# Tetris.net
KiCad netlist of a schematic drawn in EAGLE
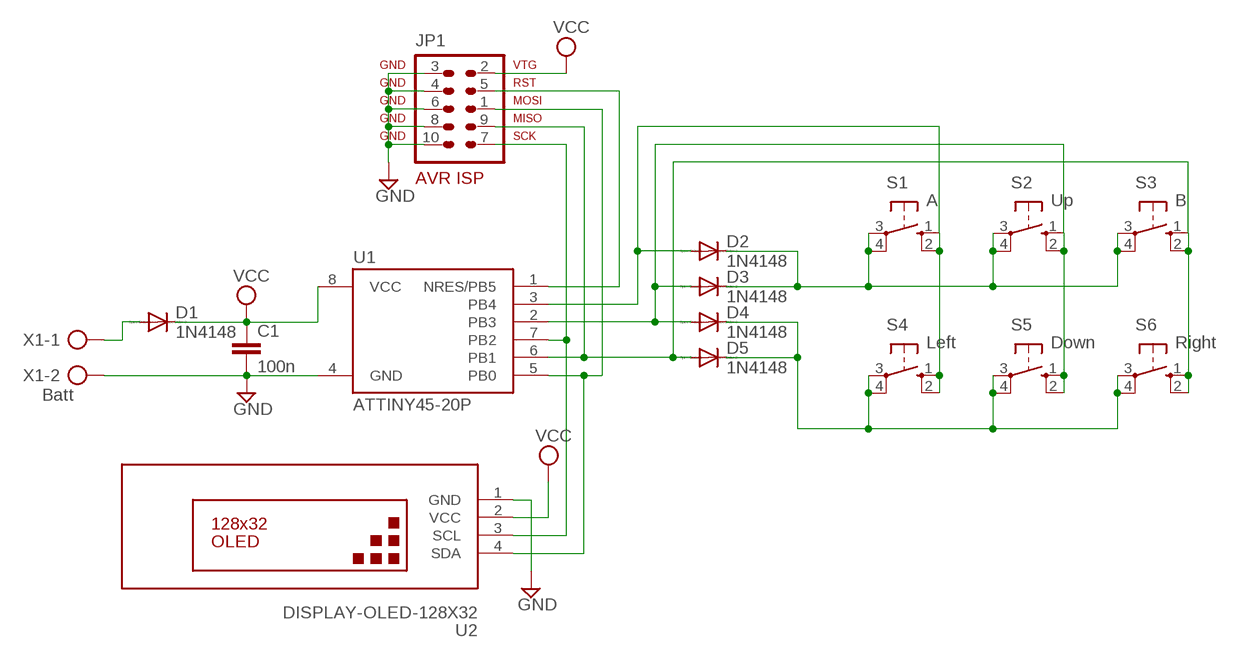
[diagram p0: schematic, sheet 1]

(export (version "E")
  (design (tool "Eeschema 10.0.6"))
  (components
    (comp (ref "C1")
      (value "100n")
      (footprint "eagle-import:C025-024X044")
      (libsource (lib "eagle-import") (part "C-EU025-024X044"))
    )
    (comp (ref "D1")
      (value "1N4148")
      (footprint "eagle-import:DO35-7")
      (libsource (lib "eagle-import") (part "1N4148DO35-7"))
    )
    (comp (ref "D2")
      (value "1N4148")
      (footprint "eagle-import:DO35-7")
      (libsource (lib "eagle-import") (part "1N4148DO35-7"))
    )
    (comp (ref "D3")
      (value "1N4148")
      (footprint "eagle-import:DO35-7")
      (libsource (lib "eagle-import") (part "1N4148DO35-7"))
    )
    (comp (ref "D4")
      (value "1N4148")
      (footprint "eagle-import:DO35-7")
      (libsource (lib "eagle-import") (part "1N4148DO35-7"))
    )
    (comp (ref "D5")
      (value "1N4148")
      (footprint "eagle-import:DO35-7")
      (libsource (lib "eagle-import") (part "1N4148DO35-7"))
    )
    (comp (ref "JP1")
      (value "AVR-ISP-10")
      (footprint "eagle-import:AVR-ISP-10")
      (libsource (lib "eagle-import") (part "AVR-ISP-10"))
    )
    (comp (ref "S1")
      (value "A")
      (footprint "eagle-import:B3F-10XX")
      (fields (field (name "MPN") "B3F-1000"))
      (libsource (lib "eagle-import") (part "10-XX"))
    )
    (comp (ref "S2")
      (value "Up")
      (footprint "eagle-import:B3F-10XX")
      (fields (field (name "MPN") "B3F-1000"))
      (libsource (lib "eagle-import") (part "10-XX"))
    )
    (comp (ref "S3")
      (value "B")
      (footprint "eagle-import:B3F-10XX")
      (fields (field (name "MPN") "B3F-1000"))
      (libsource (lib "eagle-import") (part "10-XX"))
    )
    (comp (ref "S4")
      (value "Left")
      (footprint "eagle-import:B3F-10XX")
      (fields (field (name "MPN") "B3F-1000"))
      (libsource (lib "eagle-import") (part "10-XX"))
    )
    (comp (ref "S5")
      (value "Down")
      (footprint "eagle-import:B3F-10XX")
      (fields (field (name "MPN") "B3F-1000"))
      (libsource (lib "eagle-import") (part "10-XX"))
    )
    (comp (ref "S6")
      (value "Right")
      (footprint "eagle-import:B3F-10XX")
      (fields (field (name "MPN") "B3F-1000"))
      (libsource (lib "eagle-import") (part "10-XX"))
    )
    (comp (ref "U1")
      (value "ATTINY45-20P")
      (footprint "eagle-import:PDIP08_300MIL")
      (libsource (lib "eagle-import") (part "ATTINY45P-20"))
    )
    (comp (ref "U2")
      (value "DISPLAY-OLED-128X32")
      (footprint "eagle-import:DISPLAY-OLED-128X32")
      (libsource (lib "eagle-import") (part "DISPLAY-OLED-128X32"))
    )
    (comp (ref "X1")
      (value "Batt")
      (footprint "eagle-import:AK500_2")
      (libsource (lib "eagle-import") (part "AK500/2"))
    )
  )
  (nets
    (net (code "1") (name "GND") (class "Default")
      (node (ref "C1") (pin "2") (pinfunction "2_2") (pintype "passive"))
      (node (ref "JP1") (pin "10") (pinfunction "10_10") (pintype "passive"))
      (node (ref "JP1") (pin "3") (pinfunction "3_3") (pintype "passive"))
      (node (ref "JP1") (pin "4") (pinfunction "4_4") (pintype "passive"))
      (node (ref "JP1") (pin "6") (pinfunction "6_6") (pintype "passive"))
      (node (ref "JP1") (pin "8") (pinfunction "8_8") (pintype "passive"))
      (node (ref "U1") (pin "4") (pinfunction "GND_4") (pintype "power_in"))
      (node (ref "U2") (pin "1") (pinfunction "GND_1") (pintype "power_in"))
      (node (ref "X1") (pin "2") (pinfunction "KL_2") (pintype "passive"))
    )
    (net (code "2") (name "Net-(S1-P)") (class "Default")
      (node (ref "D2") (pin "C") (pinfunction "C_C") (pintype "passive"))
      (node (ref "D3") (pin "C") (pinfunction "C_C") (pintype "passive"))
      (node (ref "S1") (pin "3") (pinfunction "P_3") (pintype "passive"))
      (node (ref "S1") (pin "4") (pinfunction "P1_4") (pintype "passive"))
      (node (ref "S2") (pin "3") (pinfunction "P_3") (pintype "passive"))
      (node (ref "S2") (pin "4") (pinfunction "P1_4") (pintype "passive"))
      (node (ref "S3") (pin "3") (pinfunction "P_3") (pintype "passive"))
      (node (ref "S3") (pin "4") (pinfunction "P1_4") (pintype "passive"))
    )
    (net (code "3") (name "Net-(S1-S)") (class "Default")
      (node (ref "D2") (pin "A") (pinfunction "A_A") (pintype "passive"))
      (node (ref "S1") (pin "1") (pinfunction "S_1") (pintype "passive"))
      (node (ref "S1") (pin "2") (pinfunction "S1_2") (pintype "passive"))
      (node (ref "S4") (pin "1") (pinfunction "S_1") (pintype "passive"))
      (node (ref "S4") (pin "2") (pinfunction "S1_2") (pintype "passive"))
      (node (ref "U1") (pin "3") (pinfunction "PB4_3") (pintype "bidirectional"))
    )
    (net (code "4") (name "Net-(S2-S)") (class "Default")
      (node (ref "D3") (pin "A") (pinfunction "A_A") (pintype "passive"))
      (node (ref "D4") (pin "A") (pinfunction "A_A") (pintype "passive"))
      (node (ref "S2") (pin "1") (pinfunction "S_1") (pintype "passive"))
      (node (ref "S2") (pin "2") (pinfunction "S1_2") (pintype "passive"))
      (node (ref "S5") (pin "1") (pinfunction "S_1") (pintype "passive"))
      (node (ref "S5") (pin "2") (pinfunction "S1_2") (pintype "passive"))
      (node (ref "U1") (pin "2") (pinfunction "PB3_2") (pintype "bidirectional"))
    )
    (net (code "5") (name "Net-(S3-S)") (class "Default")
      (node (ref "D5") (pin "A") (pinfunction "A_A") (pintype "passive"))
      (node (ref "JP1") (pin "9") (pinfunction "9_9") (pintype "passive"))
      (node (ref "S3") (pin "1") (pinfunction "S_1") (pintype "passive"))
      (node (ref "S3") (pin "2") (pinfunction "S1_2") (pintype "passive"))
      (node (ref "S6") (pin "1") (pinfunction "S_1") (pintype "passive"))
      (node (ref "S6") (pin "2") (pinfunction "S1_2") (pintype "passive"))
      (node (ref "U1") (pin "6") (pinfunction "PB1_6") (pintype "bidirectional"))
    )
    (net (code "6") (name "Net-(S4-P)") (class "Default")
      (node (ref "D4") (pin "C") (pinfunction "C_C") (pintype "passive"))
      (node (ref "D5") (pin "C") (pinfunction "C_C") (pintype "passive"))
      (node (ref "S4") (pin "3") (pinfunction "P_3") (pintype "passive"))
      (node (ref "S4") (pin "4") (pinfunction "P1_4") (pintype "passive"))
      (node (ref "S5") (pin "3") (pinfunction "P_3") (pintype "passive"))
      (node (ref "S5") (pin "4") (pinfunction "P1_4") (pintype "passive"))
      (node (ref "S6") (pin "3") (pinfunction "P_3") (pintype "passive"))
      (node (ref "S6") (pin "4") (pinfunction "P1_4") (pintype "passive"))
    )
    (net (code "7") (name "Net-(U1-NRES{slash}PB5)") (class "Default")
      (node (ref "JP1") (pin "5") (pinfunction "5_5") (pintype "passive"))
      (node (ref "U1") (pin "1") (pinfunction "NRES/PB5_1") (pintype "bidirectional"))
    )
    (net (code "8") (name "Net-(U1-PB0)") (class "Default")
      (node (ref "JP1") (pin "1") (pinfunction "1_1") (pintype "passive"))
      (node (ref "U1") (pin "5") (pinfunction "PB0_5") (pintype "bidirectional"))
      (node (ref "U2") (pin "4") (pinfunction "SDA_4") (pintype "bidirectional"))
    )
    (net (code "9") (name "Net-(U1-PB2)") (class "Default")
      (node (ref "JP1") (pin "7") (pinfunction "7_7") (pintype "passive"))
      (node (ref "U1") (pin "7") (pinfunction "PB2_7") (pintype "bidirectional"))
      (node (ref "U2") (pin "3") (pinfunction "SCL_3") (pintype "bidirectional"))
    )
    (net (code "10") (name "Net-(X1A-KL)") (class "Default")
      (node (ref "D1") (pin "A") (pinfunction "A_A") (pintype "passive"))
      (node (ref "X1") (pin "1") (pinfunction "KL_1") (pintype "passive"))
    )
    (net (code "11") (name "VCC") (class "Default")
      (node (ref "C1") (pin "1") (pinfunction "1_1") (pintype "passive"))
      (node (ref "D1") (pin "C") (pinfunction "C_C") (pintype "passive"))
      (node (ref "JP1") (pin "2") (pinfunction "2_2") (pintype "passive"))
      (node (ref "U1") (pin "8") (pinfunction "VCC_8") (pintype "power_in"))
      (node (ref "U2") (pin "2") (pinfunction "VCC_2") (pintype "power_in"))
    )
  )
)
